# Floppytron.net
KiCad netlist of a schematic drawn in Altium Designer
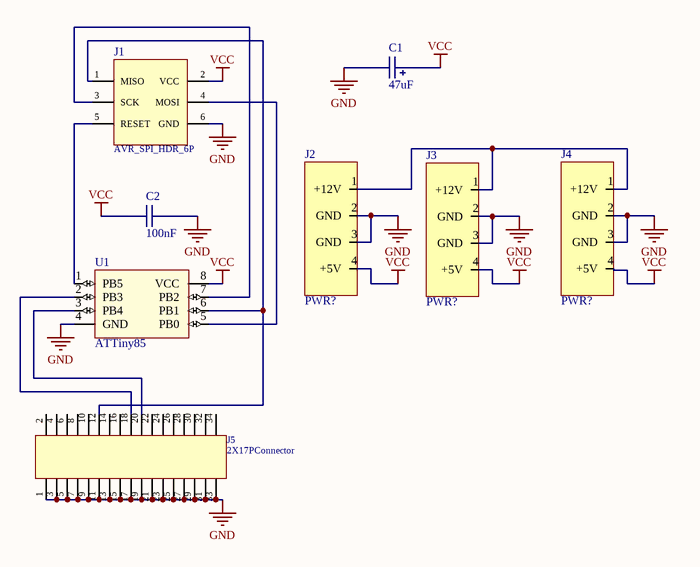
[diagram p0: Floppytron.SchDoc]

(export (version "E")
  (design (tool "Eeschema 10.0.6"))
  (components
    (comp (ref "C1")
      (value "47uF")
      (footprint "CAPPR20D05H11")
      (description "25V, Elektrolytt")
      (libsource (lib "OVLib") (part "POLCAP"))
    )
    (comp (ref "C2")
      (value "100nF")
      (footprint "CAPAR500W50L730T250H650")
      (description "100V plast")
      (libsource (lib "OVLib") (part "CAP"))
    )
    (comp (ref "J1")
      (value "AVR_SPI_HDR_6P")
      (footprint "HEADER_3x2")
      (description "6-pins ISP header for AVR")
      (libsource (lib "OVLib") (part "AVR_SPI_HDR_6P"))
    )
    (comp (ref "J2")
      (value "PWR?")
      (footprint "MOLEX_4-PIN_DISK_PWR_MALE_PCB")
      (description "4Pin PC power connector")
      (libsource (lib "OVLib") (part "MOLEX_4-PIN_DISK_PWR_MALE_PCB"))
    )
    (comp (ref "J3")
      (value "PWR?")
      (footprint "MOLEX_4-PIN_DISK_PWR_MALE_PCB")
      (description "4Pin PC power connector")
      (libsource (lib "OVLib") (part "MOLEX_4-PIN_DISK_PWR_MALE_PCB"))
    )
    (comp (ref "J4")
      (value "PWR?")
      (footprint "MOLEX_4-PIN_DISK_PWR_MALE_PCB")
      (description "4Pin PC power connector")
      (libsource (lib "OVLib") (part "MOLEX_4-PIN_DISK_PWR_MALE_PCB"))
    )
    (comp (ref "J5")
      (value "2X17PConnector")
      (footprint "HDRV34W64P254_2X17_5070X900X900B")
      (libsource (lib "OVLib") (part "2X17PConnector"))
    )
    (comp (ref "U1") (value "ATTiny85") (footprint "DIP8") (libsource (lib "ATTINY85") (part "ATTiny85")))
  )
  (nets
    (net (code "1") (name "GND") (class "Default")
      (node (ref "C1") (pin "1") (pinfunction "1_1") (pintype "passive"))
      (node (ref "C2") (pin "2") (pinfunction "2_2") (pintype "passive"))
      (node (ref "J1") (pin "6") (pinfunction "GND_6") (pintype "passive"))
      (node (ref "J2") (pin "2") (pinfunction "GND_2") (pintype "passive"))
      (node (ref "J2") (pin "3") (pinfunction "GND_3") (pintype "passive"))
      (node (ref "J3") (pin "2") (pinfunction "GND_2") (pintype "passive"))
      (node (ref "J3") (pin "3") (pinfunction "GND_3") (pintype "passive"))
      (node (ref "J4") (pin "2") (pinfunction "GND_2") (pintype "passive"))
      (node (ref "J4") (pin "3") (pinfunction "GND_3") (pintype "passive"))
      (node (ref "J5") (pin "1") (pinfunction "1_1") (pintype "passive"))
      (node (ref "J5") (pin "11") (pinfunction "11_11") (pintype "passive"))
      (node (ref "J5") (pin "13") (pinfunction "13_13") (pintype "passive"))
      (node (ref "J5") (pin "15") (pinfunction "15_15") (pintype "passive"))
      (node (ref "J5") (pin "17") (pinfunction "17_17") (pintype "passive"))
      (node (ref "J5") (pin "19") (pinfunction "19_19") (pintype "passive"))
      (node (ref "J5") (pin "21") (pinfunction "21_21") (pintype "passive"))
      (node (ref "J5") (pin "23") (pinfunction "23_23") (pintype "passive"))
      (node (ref "J5") (pin "25") (pinfunction "25_25") (pintype "passive"))
      (node (ref "J5") (pin "27") (pinfunction "27_27") (pintype "passive"))
      (node (ref "J5") (pin "29") (pinfunction "29_29") (pintype "passive"))
      (node (ref "J5") (pin "3") (pinfunction "3_3") (pintype "passive"))
      (node (ref "J5") (pin "31") (pinfunction "31_31") (pintype "passive"))
      (node (ref "J5") (pin "33") (pinfunction "33_33") (pintype "passive"))
      (node (ref "J5") (pin "5") (pinfunction "5_5") (pintype "passive"))
      (node (ref "J5") (pin "7") (pinfunction "7_7") (pintype "passive"))
      (node (ref "J5") (pin "9") (pinfunction "9_9") (pintype "passive"))
      (node (ref "U1") (pin "4") (pinfunction "GND_4") (pintype "power_in"))
    )
    (net (code "2") (name "Net-(J1-MISO)") (class "Default")
      (node (ref "J1") (pin "1") (pinfunction "MISO_1") (pintype "passive"))
      (node (ref "J5") (pin "12") (pinfunction "12_12") (pintype "passive"))
      (node (ref "U1") (pin "6") (pinfunction "PB1_6") (pintype "bidirectional"))
    )
    (net (code "3") (name "Net-(J1-MOSI)") (class "Default")
      (node (ref "J1") (pin "4") (pinfunction "MOSI_4") (pintype "passive"))
      (node (ref "U1") (pin "5") (pinfunction "PB0_5") (pintype "bidirectional"))
    )
    (net (code "4") (name "Net-(J1-RESET)") (class "Default")
      (node (ref "J1") (pin "5") (pinfunction "RESET_5") (pintype "passive"))
      (node (ref "U1") (pin "1") (pinfunction "PB5_1") (pintype "bidirectional"))
    )
    (net (code "5") (name "Net-(J1-SCK)") (class "Default")
      (node (ref "J1") (pin "3") (pinfunction "SCK_3") (pintype "passive"))
      (node (ref "U1") (pin "7") (pinfunction "PB2_7") (pintype "bidirectional"))
    )
    (net (code "6") (name "Net-(J2-+12V)") (class "Default")
      (node (ref "J2") (pin "1") (pinfunction "+12V_1") (pintype "power_in"))
      (node (ref "J3") (pin "1") (pinfunction "+12V_1") (pintype "power_in"))
      (node (ref "J4") (pin "1") (pinfunction "+12V_1") (pintype "power_in"))
    )
    (net (code "7") (name "Net-(U1-PB3)") (class "Default")
      (node (ref "J5") (pin "18") (pinfunction "18_18") (pintype "passive"))
      (node (ref "U1") (pin "2") (pinfunction "PB3_2") (pintype "bidirectional"))
    )
    (net (code "8") (name "Net-(U1-PB4)") (class "Default")
      (node (ref "J5") (pin "20") (pinfunction "20_20") (pintype "passive"))
      (node (ref "U1") (pin "3") (pinfunction "PB4_3") (pintype "bidirectional"))
    )
    (net (code "9") (name "VCC") (class "Default")
      (node (ref "C1") (pin "2") (pinfunction "2_2") (pintype "passive"))
      (node (ref "C2") (pin "1") (pinfunction "1_1") (pintype "passive"))
      (node (ref "J1") (pin "2") (pinfunction "VCC_2") (pintype "passive"))
      (node (ref "J2") (pin "4") (pinfunction "+5V_4") (pintype "power_in"))
      (node (ref "J3") (pin "4") (pinfunction "+5V_4") (pintype "power_in"))
      (node (ref "J4") (pin "4") (pinfunction "+5V_4") (pintype "power_in"))
      (node (ref "U1") (pin "8") (pinfunction "VCC_8") (pintype "power_in"))
    )
    (net (code "10") (name "unconnected-(J5-Pad2)") (class "Default")
      (node (ref "J5") (pin "2") (pinfunction "2_2") (pintype "passive"))
    )
    (net (code "11") (name "unconnected-(J5-Pad4)") (class "Default")
      (node (ref "J5") (pin "4") (pinfunction "4_4") (pintype "passive"))
    )
    (net (code "12") (name "unconnected-(J5-Pad6)") (class "Default")
      (node (ref "J5") (pin "6") (pinfunction "6_6") (pintype "passive"))
    )
    (net (code "13") (name "unconnected-(J5-Pad8)") (class "Default")
      (node (ref "J5") (pin "8") (pinfunction "8_8") (pintype "passive"))
    )
    (net (code "14") (name "unconnected-(J5-Pad10)") (class "Default")
      (node (ref "J5") (pin "10") (pinfunction "10_10") (pintype "passive"))
    )
    (net (code "15") (name "unconnected-(J5-Pad14)") (class "Default")
      (node (ref "J5") (pin "14") (pinfunction "14_14") (pintype "passive"))
    )
    (net (code "16") (name "unconnected-(J5-Pad16)") (class "Default")
      (node (ref "J5") (pin "16") (pinfunction "16_16") (pintype "passive"))
    )
    (net (code "17") (name "unconnected-(J5-Pad22)") (class "Default")
      (node (ref "J5") (pin "22") (pinfunction "22_22") (pintype "passive"))
    )
    (net (code "18") (name "unconnected-(J5-Pad24)") (class "Default")
      (node (ref "J5") (pin "24") (pinfunction "24_24") (pintype "passive"))
    )
    (net (code "19") (name "unconnected-(J5-Pad26)") (class "Default")
      (node (ref "J5") (pin "26") (pinfunction "26_26") (pintype "passive"))
    )
    (net (code "20") (name "unconnected-(J5-Pad28)") (class "Default")
      (node (ref "J5") (pin "28") (pinfunction "28_28") (pintype "passive"))
    )
    (net (code "21") (name "unconnected-(J5-Pad30)") (class "Default")
      (node (ref "J5") (pin "30") (pinfunction "30_30") (pintype "passive"))
    )
    (net (code "22") (name "unconnected-(J5-Pad32)") (class "Default")
      (node (ref "J5") (pin "32") (pinfunction "32_32") (pintype "passive"))
    )
    (net (code "23") (name "unconnected-(J5-Pad34)") (class "Default")
      (node (ref "J5") (pin "34") (pinfunction "34_34") (pintype "passive"))
    )
  )
)
